# Power.net
KiCad netlist of a schematic drawn in Altium Designer
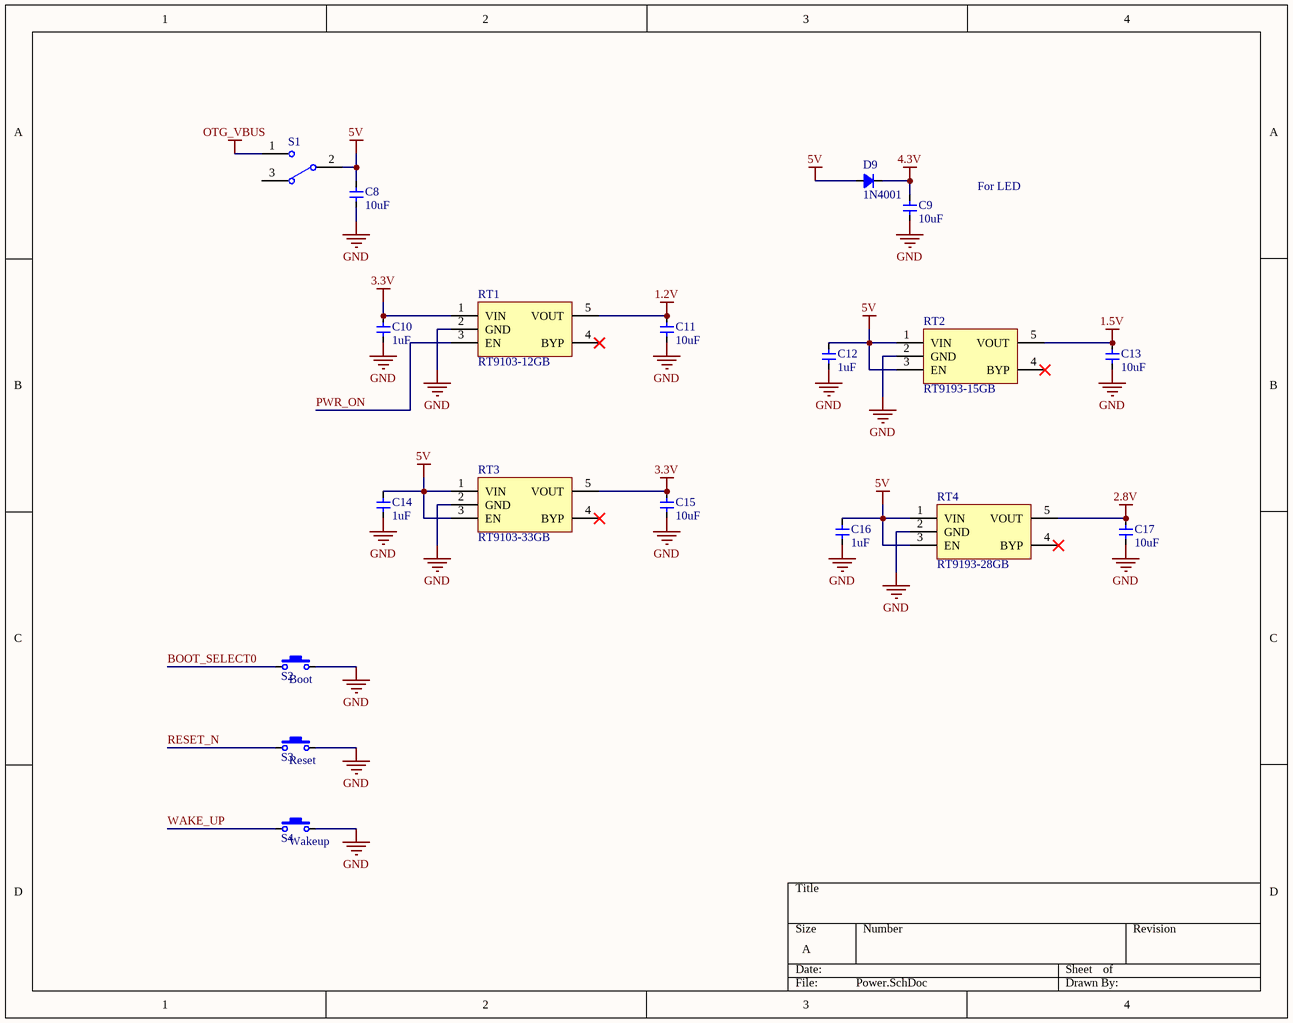
[diagram p0: Power.SchDoc]

(export (version "E")
  (design (tool "Eeschema 10.0.6"))
  (components
    (comp (ref "C8")
      (value "10uF")
      (footprint "PCB_PassiveCap:CAP_0805")
      (description "Capacitor")
      (fields (field (name "Comment") "Cap_0805"))
      (libsource (lib "SCH_Passive") (part "Cap_0805"))
    )
    (comp (ref "C9")
      (value "10uF")
      (footprint "PCB_PassiveCap:CAP_0805")
      (description "Capacitor")
      (fields (field (name "Comment") "Cap_0805"))
      (libsource (lib "SCH_Passive") (part "Cap_0805"))
    )
    (comp (ref "C10")
      (value "1uF")
      (footprint "PCB_PassiveCap:CAP_0402")
      (description "Capacitor")
      (fields (field (name "Comment") "Cap_0402"))
      (libsource (lib "SCH_Passive") (part "Cap_0402"))
    )
    (comp (ref "C11")
      (value "10uF")
      (footprint "PCB_PassiveCap:CAP_0805")
      (description "Capacitor")
      (fields (field (name "Comment") "Cap_0805"))
      (libsource (lib "SCH_Passive") (part "Cap_0805"))
    )
    (comp (ref "C12")
      (value "1uF")
      (footprint "PCB_PassiveCap:CAP_0402")
      (description "Capacitor")
      (fields (field (name "Comment") "Cap_0402"))
      (libsource (lib "SCH_Passive") (part "Cap_0402"))
    )
    (comp (ref "C13")
      (value "10uF")
      (footprint "PCB_PassiveCap:CAP_0805")
      (description "Capacitor")
      (fields (field (name "Comment") "Cap_0805"))
      (libsource (lib "SCH_Passive") (part "Cap_0805"))
    )
    (comp (ref "C14")
      (value "1uF")
      (footprint "PCB_PassiveCap:CAP_0402")
      (description "Capacitor")
      (fields (field (name "Comment") "Cap_0402"))
      (libsource (lib "SCH_Passive") (part "Cap_0402"))
    )
    (comp (ref "C15")
      (value "10uF")
      (footprint "PCB_PassiveCap:CAP_0805")
      (description "Capacitor")
      (fields (field (name "Comment") "Cap_0805"))
      (libsource (lib "SCH_Passive") (part "Cap_0805"))
    )
    (comp (ref "C16")
      (value "1uF")
      (footprint "PCB_PassiveCap:CAP_0402")
      (description "Capacitor")
      (fields (field (name "Comment") "Cap_0402"))
      (libsource (lib "SCH_Passive") (part "Cap_0402"))
    )
    (comp (ref "C17")
      (value "10uF")
      (footprint "PCB_PassiveCap:CAP_0805")
      (description "Capacitor")
      (fields (field (name "Comment") "Cap_0805"))
      (libsource (lib "SCH_Passive") (part "Cap_0805"))
    )
    (comp (ref "D9")
      (value "1N4001")
      (footprint "PCB_ActiveDIO:DO-214AC")
      (description "Diode")
      (fields (field (name "Comment") "IN4001"))
      (libsource (lib "SCH_Active") (part "Diode_SMA"))
    )
    (comp (ref "RT1")
      (value "RT9103-12GB")
      (footprint "PCB_IntegratedCircuit:SOT23-5")
      (description "Power")
      (libsource (lib "SCH_IntegratedCircuit") (part "RT9193"))
    )
    (comp (ref "RT2")
      (value "RT9193-15GB")
      (footprint "PCB_IntegratedCircuit:SOT23-5")
      (description "Power")
      (libsource (lib "SCH_IntegratedCircuit") (part "RT9193"))
    )
    (comp (ref "RT3")
      (value "RT9103-33GB")
      (footprint "PCB_IntegratedCircuit:SOT23-5")
      (description "Power")
      (libsource (lib "SCH_IntegratedCircuit") (part "RT9193"))
    )
    (comp (ref "RT4")
      (value "RT9193-28GB")
      (footprint "PCB_IntegratedCircuit:SOT23-5")
      (description "Power")
      (libsource (lib "SCH_IntegratedCircuit") (part "RT9193"))
    )
    (comp (ref "S1")
      (value "SwitchSPDT_2.8x6.6_90")
      (footprint "PCB_Switch:SwitchSPDT_2.8X6.6_90")
      (description "Switch")
      (libsource (lib "SCH_Switch") (part "SwitchSPDT_2.8x6.6_90"))
    )
    (comp (ref "S2")
      (value "Boot")
      (footprint "PCB_Switch:ButtonTACT_3x4x2_180H")
      (description "Button")
      (libsource (lib "SCH_Switch") (part "ButtonTACT_3x4x2_180"))
    )
    (comp (ref "S3")
      (value "Reset")
      (footprint "PCB_Switch:ButtonTACT_3x4x2_180H")
      (description "Button")
      (libsource (lib "SCH_Switch") (part "ButtonTACT_3x4x2_180"))
    )
    (comp (ref "S4")
      (value "Wakeup")
      (footprint "PCB_Switch:ButtonTACT_3x4x2_180H")
      (description "Button")
      (libsource (lib "SCH_Switch") (part "ButtonTACT_3x4x2_180"))
    )
  )
  (nets
    (net (code "1") (name "/BOOT_SELECT0") (class "Default")
      (node (ref "S2") (pin "1") (pinfunction "1_1") (pintype "passive"))
    )
    (net (code "2") (name "/PWR_ON") (class "Default")
      (node (ref "RT1") (pin "3") (pinfunction "EN_3") (pintype "power_in"))
    )
    (net (code "3") (name "/RESET_N") (class "Default")
      (node (ref "S3") (pin "1") (pinfunction "1_1") (pintype "passive"))
    )
    (net (code "4") (name "/WAKE_UP") (class "Default")
      (node (ref "S4") (pin "1") (pinfunction "1_1") (pintype "passive"))
    )
    (net (code "5") (name "1.2V") (class "Default")
      (node (ref "C11") (pin "2") (pinfunction "2_2") (pintype "passive"))
      (node (ref "RT1") (pin "5") (pinfunction "VOUT_5") (pintype "passive"))
    )
    (net (code "6") (name "1.5V") (class "Default")
      (node (ref "C13") (pin "2") (pinfunction "2_2") (pintype "passive"))
      (node (ref "RT2") (pin "5") (pinfunction "VOUT_5") (pintype "passive"))
    )
    (net (code "7") (name "2.8V") (class "Default")
      (node (ref "C17") (pin "2") (pinfunction "2_2") (pintype "passive"))
      (node (ref "RT4") (pin "5") (pinfunction "VOUT_5") (pintype "passive"))
    )
    (net (code "8") (name "3.3V") (class "Default")
      (node (ref "C10") (pin "2") (pinfunction "2_2") (pintype "passive"))
      (node (ref "C15") (pin "2") (pinfunction "2_2") (pintype "passive"))
      (node (ref "RT1") (pin "1") (pinfunction "VIN_1") (pintype "passive"))
      (node (ref "RT3") (pin "5") (pinfunction "VOUT_5") (pintype "passive"))
    )
    (net (code "9") (name "4.3V") (class "Default")
      (node (ref "C9") (pin "2") (pinfunction "2_2") (pintype "passive"))
      (node (ref "D9") (pin "2") (pinfunction "K_2") (pintype "passive"))
    )
    (net (code "10") (name "5V") (class "Default")
      (node (ref "C12") (pin "2") (pinfunction "2_2") (pintype "passive"))
      (node (ref "C14") (pin "2") (pinfunction "2_2") (pintype "passive"))
      (node (ref "C16") (pin "2") (pinfunction "2_2") (pintype "passive"))
      (node (ref "C8") (pin "2") (pinfunction "2_2") (pintype "passive"))
      (node (ref "D9") (pin "1") (pinfunction "A_1") (pintype "passive"))
      (node (ref "RT2") (pin "1") (pinfunction "VIN_1") (pintype "passive"))
      (node (ref "RT2") (pin "3") (pinfunction "EN_3") (pintype "power_in"))
      (node (ref "RT3") (pin "1") (pinfunction "VIN_1") (pintype "passive"))
      (node (ref "RT3") (pin "3") (pinfunction "EN_3") (pintype "power_in"))
      (node (ref "RT4") (pin "1") (pinfunction "VIN_1") (pintype "passive"))
      (node (ref "RT4") (pin "3") (pinfunction "EN_3") (pintype "power_in"))
      (node (ref "S1") (pin "2") (pinfunction "2_2") (pintype "passive"))
    )
    (net (code "11") (name "GND") (class "Default")
      (node (ref "C10") (pin "1") (pinfunction "1_1") (pintype "passive"))
      (node (ref "C11") (pin "1") (pinfunction "1_1") (pintype "passive"))
      (node (ref "C12") (pin "1") (pinfunction "1_1") (pintype "passive"))
      (node (ref "C13") (pin "1") (pinfunction "1_1") (pintype "passive"))
      (node (ref "C14") (pin "1") (pinfunction "1_1") (pintype "passive"))
      (node (ref "C15") (pin "1") (pinfunction "1_1") (pintype "passive"))
      (node (ref "C16") (pin "1") (pinfunction "1_1") (pintype "passive"))
      (node (ref "C17") (pin "1") (pinfunction "1_1") (pintype "passive"))
      (node (ref "C8") (pin "1") (pinfunction "1_1") (pintype "passive"))
      (node (ref "C9") (pin "1") (pinfunction "1_1") (pintype "passive"))
      (node (ref "RT1") (pin "2") (pinfunction "GND_2") (pintype "passive"))
      (node (ref "RT2") (pin "2") (pinfunction "GND_2") (pintype "passive"))
      (node (ref "RT3") (pin "2") (pinfunction "GND_2") (pintype "passive"))
      (node (ref "RT4") (pin "2") (pinfunction "GND_2") (pintype "passive"))
      (node (ref "S2") (pin "2") (pinfunction "2_2") (pintype "passive"))
      (node (ref "S3") (pin "2") (pinfunction "2_2") (pintype "passive"))
      (node (ref "S4") (pin "2") (pinfunction "2_2") (pintype "passive"))
    )
    (net (code "12") (name "OTG_VBUS") (class "Default")
      (node (ref "S1") (pin "1") (pinfunction "1_1") (pintype "passive"))
    )
    (net (code "13") (name "unconnected-(RT1-BYP-Pad4)") (class "Default")
      (node (ref "RT1") (pin "4") (pinfunction "BYP_4") (pintype "passive+no_connect"))
    )
    (net (code "14") (name "unconnected-(RT2-BYP-Pad4)") (class "Default")
      (node (ref "RT2") (pin "4") (pinfunction "BYP_4") (pintype "passive+no_connect"))
    )
    (net (code "15") (name "unconnected-(RT3-BYP-Pad4)") (class "Default")
      (node (ref "RT3") (pin "4") (pinfunction "BYP_4") (pintype "passive+no_connect"))
    )
    (net (code "16") (name "unconnected-(RT4-BYP-Pad4)") (class "Default")
      (node (ref "RT4") (pin "4") (pinfunction "BYP_4") (pintype "passive+no_connect"))
    )
    (net (code "17") (name "unconnected-(S1-Pad3)") (class "Default")
      (node (ref "S1") (pin "3") (pinfunction "3_3") (pintype "passive"))
    )
  )
)
